# mgr.net
KiCad netlist of a schematic drawn in EAGLE
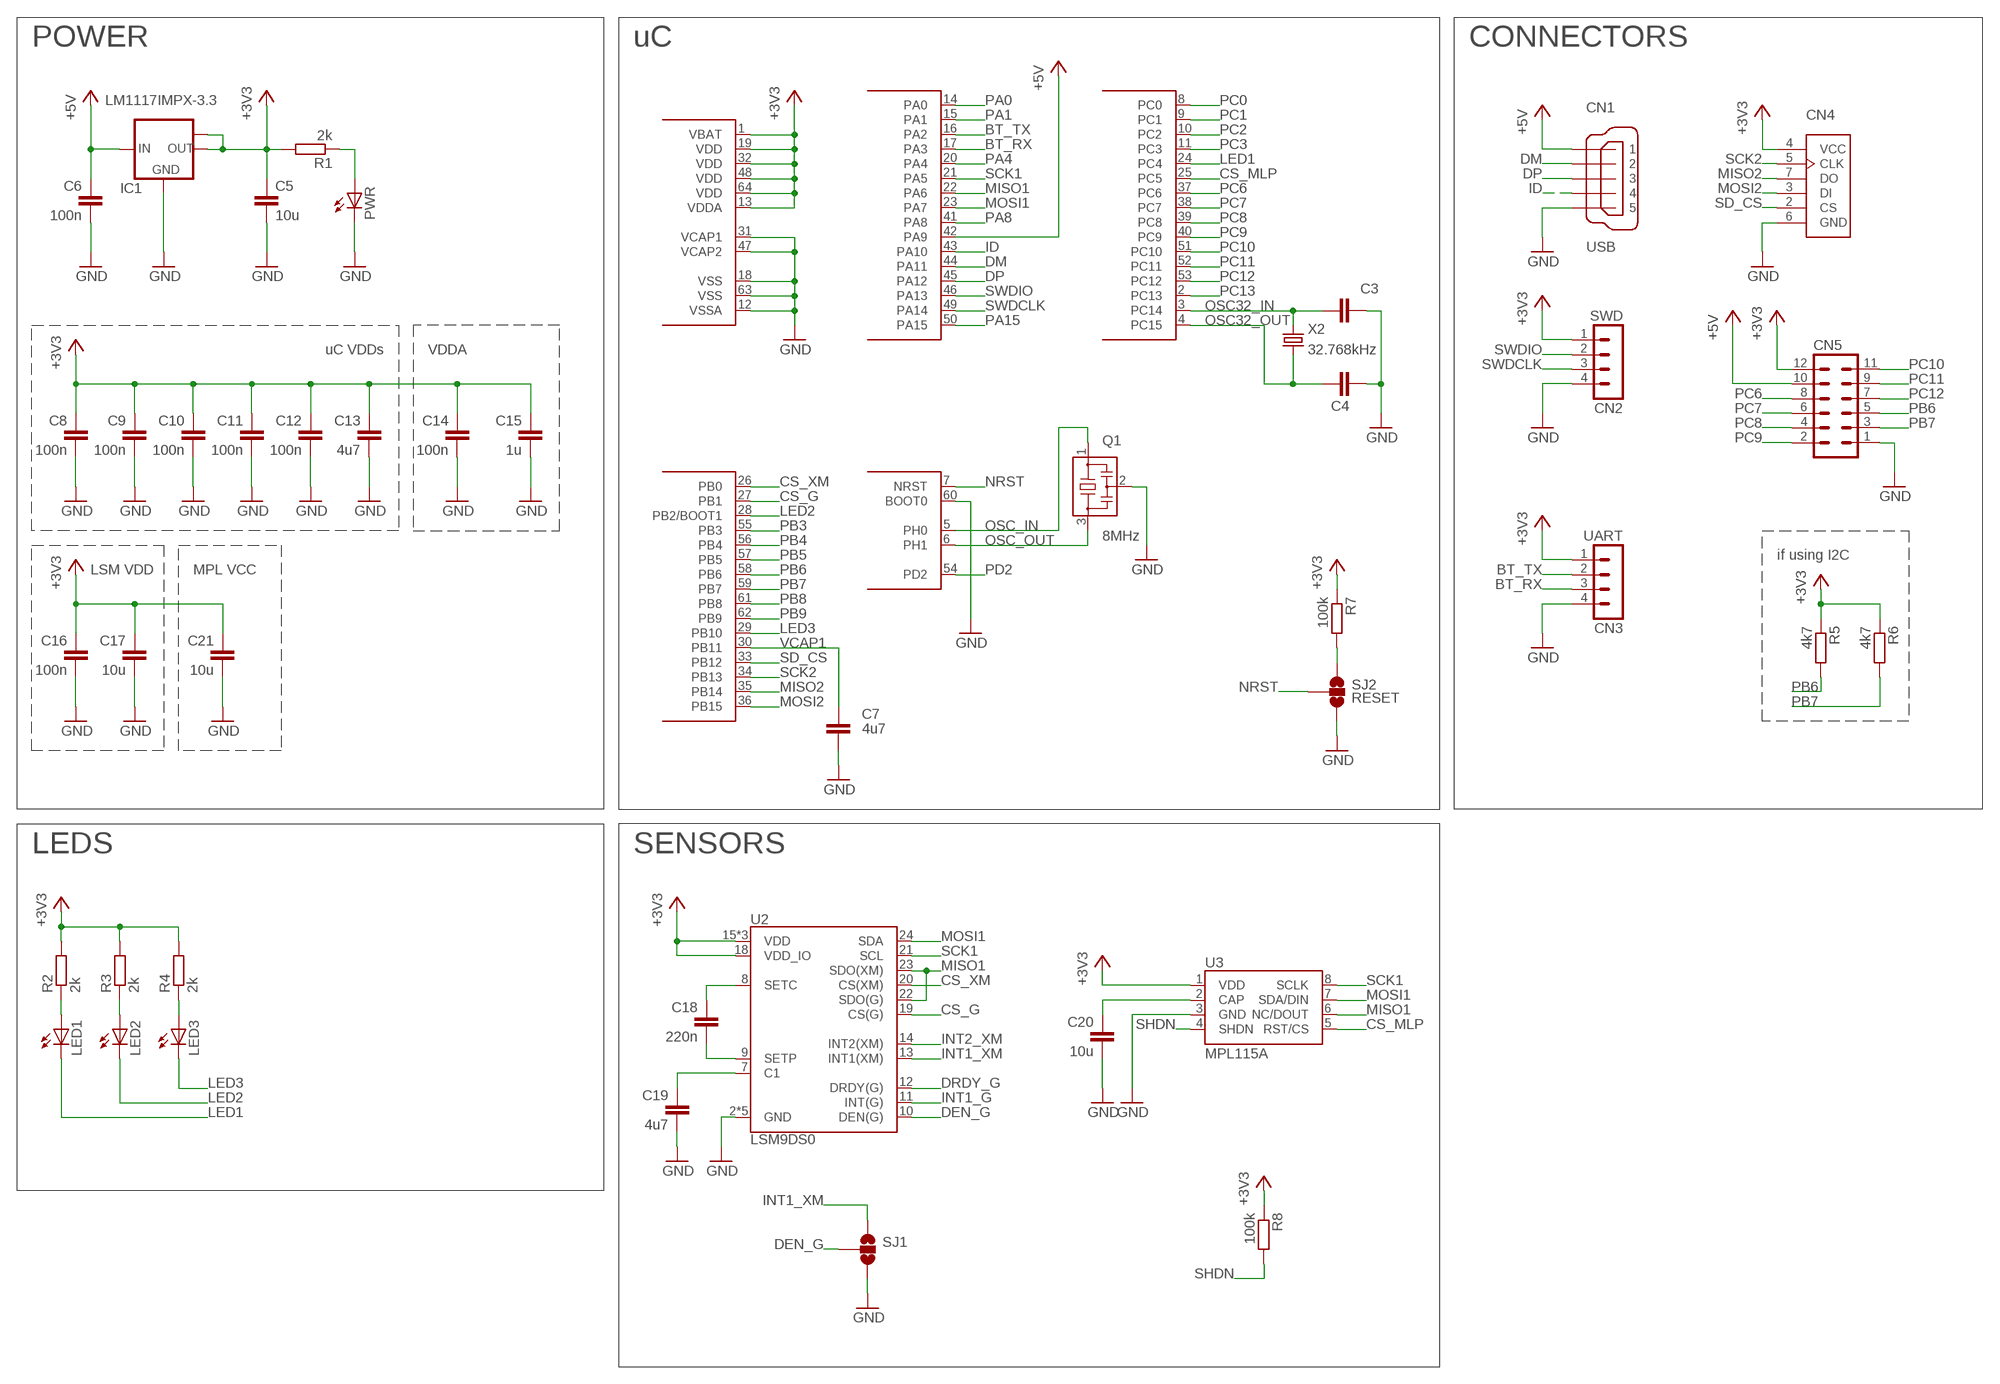
[diagram p0: schematic, sheet 1]

(export (version "E")
  (design (tool "Eeschema 10.0.6"))
  (components
    (comp (ref "C3")
      (value "C-EUC0603K")
      (footprint "eagle-import:C0603K")
      (libsource (lib "eagle-import") (part "C-EUC0603K"))
    )
    (comp (ref "C4")
      (value "C-EUC0603K")
      (footprint "eagle-import:C0603K")
      (libsource (lib "eagle-import") (part "C-EUC0603K"))
    )
    (comp (ref "C5")
      (value "10u")
      (footprint "eagle-import:C0603K")
      (libsource (lib "eagle-import") (part "C-EUC0603K"))
    )
    (comp (ref "C6")
      (value "100n")
      (footprint "eagle-import:C0603K")
      (libsource (lib "eagle-import") (part "C-EUC0603K"))
    )
    (comp (ref "C7")
      (value "4u7")
      (footprint "eagle-import:C0603K")
      (libsource (lib "eagle-import") (part "C-EUC0603K"))
    )
    (comp (ref "C8")
      (value "100n")
      (footprint "eagle-import:C0603K")
      (libsource (lib "eagle-import") (part "C-EUC0603K"))
    )
    (comp (ref "C9")
      (value "100n")
      (footprint "eagle-import:C0603K")
      (libsource (lib "eagle-import") (part "C-EUC0603K"))
    )
    (comp (ref "C10")
      (value "100n")
      (footprint "eagle-import:C0603K")
      (libsource (lib "eagle-import") (part "C-EUC0603K"))
    )
    (comp (ref "C11")
      (value "100n")
      (footprint "eagle-import:C0603K")
      (libsource (lib "eagle-import") (part "C-EUC0603K"))
    )
    (comp (ref "C12")
      (value "100n")
      (footprint "eagle-import:C0603K")
      (libsource (lib "eagle-import") (part "C-EUC0603K"))
    )
    (comp (ref "C13")
      (value "4u7")
      (footprint "eagle-import:C0603K")
      (libsource (lib "eagle-import") (part "C-EUC0603K"))
    )
    (comp (ref "C14")
      (value "100n")
      (footprint "eagle-import:C0603K")
      (libsource (lib "eagle-import") (part "C-EUC0603K"))
    )
    (comp (ref "C15")
      (value "1u")
      (footprint "eagle-import:C0603K")
      (libsource (lib "eagle-import") (part "C-EUC0603K"))
    )
    (comp (ref "C16")
      (value "100n")
      (footprint "eagle-import:C0603K")
      (libsource (lib "eagle-import") (part "C-EUC0603K"))
    )
    (comp (ref "C17")
      (value "10u")
      (footprint "eagle-import:C0603K")
      (libsource (lib "eagle-import") (part "C-EUC0603K"))
    )
    (comp (ref "C18")
      (value "220n")
      (footprint "eagle-import:C0603K")
      (libsource (lib "eagle-import") (part "C-EUC0603K"))
    )
    (comp (ref "C19")
      (value "4u7")
      (footprint "eagle-import:C0603K")
      (libsource (lib "eagle-import") (part "C-EUC0603K"))
    )
    (comp (ref "C20")
      (value "10u")
      (footprint "eagle-import:C0603K")
      (libsource (lib "eagle-import") (part "C-EUC0603K"))
    )
    (comp (ref "C21")
      (value "10u")
      (footprint "eagle-import:C0603K")
      (libsource (lib "eagle-import") (part "C-EUC0603K"))
    )
    (comp (ref "CN1")
      (value "USB")
      (footprint "eagle-import:UX60-MB-5ST")
      (libsource (lib "eagle-import") (part "MINI-USB-UX60-MB-5ST"))
    )
    (comp (ref "CN2")
      (value "SWD")
      (footprint "eagle-import:MA04-1")
      (libsource (lib "eagle-import") (part "MA04-1"))
    )
    (comp (ref "CN3")
      (value "UART")
      (footprint "eagle-import:MA04-1")
      (libsource (lib "eagle-import") (part "MA04-1"))
    )
    (comp (ref "CN4")
      (value "MICRO_SD_CONNECTOR")
      (footprint "eagle-import:MICROSD_CONNECTOR")
      (libsource (lib "eagle-import") (part "MICRO_SD_CONNECTOR"))
    )
    (comp (ref "CN5")
      (value "MA06-2")
      (footprint "eagle-import:MA06-2")
      (libsource (lib "eagle-import") (part "MA06-2"))
    )
    (comp (ref "IC1")
      (value "LM1117IMPX-3.3")
      (footprint "eagle-import:SOT223")
      (libsource (lib "eagle-import") (part "LM1117IMPX-3.3"))
    )
    (comp (ref "LED1")
      (value "LEDSML0603")
      (footprint "eagle-import:SML0603")
      (libsource (lib "eagle-import") (part "LEDSML0603"))
    )
    (comp (ref "LED2")
      (value "LEDSML0603")
      (footprint "eagle-import:SML0603")
      (libsource (lib "eagle-import") (part "LEDSML0603"))
    )
    (comp (ref "LED3")
      (value "LEDSML0603")
      (footprint "eagle-import:SML0603")
      (libsource (lib "eagle-import") (part "LEDSML0603"))
    )
    (comp (ref "PWR")
      (value "LEDSML0603")
      (footprint "eagle-import:SML0603")
      (libsource (lib "eagle-import") (part "LEDSML0603"))
    )
    (comp (ref "Q1")
      (value "8MHz")
      (footprint "eagle-import:CSTCR6M")
      (fields (field (name "MPN") "CSTCR6M00G53-R0"))
      (libsource (lib "eagle-import") (part "CSTCR6M00G53Z"))
    )
    (comp (ref "R1")
      (value "2k")
      (footprint "eagle-import:R0603")
      (libsource (lib "eagle-import") (part "R-EU_R0603"))
    )
    (comp (ref "R2")
      (value "2k")
      (footprint "eagle-import:R0603")
      (libsource (lib "eagle-import") (part "R-EU_R0603"))
    )
    (comp (ref "R3")
      (value "2k")
      (footprint "eagle-import:R0603")
      (libsource (lib "eagle-import") (part "R-EU_R0603"))
    )
    (comp (ref "R4")
      (value "2k")
      (footprint "eagle-import:R0603")
      (libsource (lib "eagle-import") (part "R-EU_R0603"))
    )
    (comp (ref "R5")
      (value "4k7")
      (footprint "eagle-import:R0603")
      (libsource (lib "eagle-import") (part "R-EU_R0603"))
    )
    (comp (ref "R6")
      (value "4k7")
      (footprint "eagle-import:R0603")
      (libsource (lib "eagle-import") (part "R-EU_R0603"))
    )
    (comp (ref "R7")
      (value "100k")
      (footprint "eagle-import:R0603")
      (libsource (lib "eagle-import") (part "R-EU_R0603"))
    )
    (comp (ref "R8")
      (value "100k")
      (footprint "eagle-import:R0603")
      (libsource (lib "eagle-import") (part "R-EU_R0603"))
    )
    (comp (ref "SJ1")
      (value "JUMPER-PAD-3-NOYES_SILK")
      (footprint "eagle-import:PAD-JUMPER-3-NO_YES_SILK")
      (libsource (lib "eagle-import") (part "JUMPER-PAD-3-NOYES_SILK"))
    )
    (comp (ref "SJ2")
      (value "RESET")
      (footprint "eagle-import:PAD-JUMPER-3-NO_YES_SILK")
      (libsource (lib "eagle-import") (part "JUMPER-PAD-3-NOYES_SILK"))
    )
    (comp (ref "U1")
      (value "STM32F4-64")
      (footprint "eagle-import:SQFP-S-10X10-64")
      (libsource (lib "eagle-import") (part "STM32F4-64"))
    )
    (comp (ref "U2")
      (value "LSM9DS0")
      (footprint "eagle-import:LGA-24")
      (libsource (lib "eagle-import") (part "LSM9DS0"))
    )
    (comp (ref "U3")
      (value "MPL115A")
      (footprint "eagle-import:LGA8")
      (libsource (lib "eagle-import") (part "MPL115A"))
    )
    (comp (ref "X2")
      (value "32.768kHz")
      (footprint "eagle-import:3.2X1.5-2-PAD")
      (libsource (lib "eagle-import") (part "CRYSTALS-NOGND-CFPX-217"))
    )
  )
  (nets
    (net (code "1") (name "+3V3") (class "Default")
      (node (ref "C10") (pin "2") (pinfunction "2_2") (pintype "passive"))
      (node (ref "C11") (pin "2") (pinfunction "2_2") (pintype "passive"))
      (node (ref "C12") (pin "2") (pinfunction "2_2") (pintype "passive"))
      (node (ref "C13") (pin "2") (pinfunction "2_2") (pintype "passive"))
      (node (ref "C14") (pin "2") (pinfunction "2_2") (pintype "passive"))
      (node (ref "C15") (pin "2") (pinfunction "2_2") (pintype "passive"))
      (node (ref "C16") (pin "2") (pinfunction "2_2") (pintype "passive"))
      (node (ref "C17") (pin "2") (pinfunction "2_2") (pintype "passive"))
      (node (ref "C21") (pin "2") (pinfunction "2_2") (pintype "passive"))
      (node (ref "C5") (pin "2") (pinfunction "2_2") (pintype "passive"))
      (node (ref "C8") (pin "2") (pinfunction "2_2") (pintype "passive"))
      (node (ref "C9") (pin "2") (pinfunction "2_2") (pintype "passive"))
      (node (ref "CN2") (pin "1") (pinfunction "1_1") (pintype "passive"))
      (node (ref "CN3") (pin "1") (pinfunction "1_1") (pintype "passive"))
      (node (ref "CN4") (pin "4") (pinfunction "VCC_4") (pintype "power_in"))
      (node (ref "CN5") (pin "12") (pinfunction "12_12") (pintype "passive"))
      (node (ref "IC1") (pin "2") (pinfunction "OUT_2") (pintype "passive"))
      (node (ref "IC1") (pin "TAB") (pinfunction "OUT1_TAB") (pintype "passive"))
      (node (ref "R1") (pin "2") (pinfunction "2_2") (pintype "passive"))
      (node (ref "R2") (pin "2") (pinfunction "2_2") (pintype "passive"))
      (node (ref "R3") (pin "2") (pinfunction "2_2") (pintype "passive"))
      (node (ref "R4") (pin "2") (pinfunction "2_2") (pintype "passive"))
      (node (ref "R5") (pin "1") (pinfunction "1_1") (pintype "passive"))
      (node (ref "R6") (pin "1") (pinfunction "1_1") (pintype "passive"))
      (node (ref "R7") (pin "1") (pinfunction "1_1") (pintype "passive"))
      (node (ref "R8") (pin "1") (pinfunction "1_1") (pintype "passive"))
      (node (ref "U1") (pin "1") (pinfunction "VBAT_1") (pintype "power_in"))
      (node (ref "U1") (pin "13") (pinfunction "VDDA_13") (pintype "power_in"))
      (node (ref "U1") (pin "19") (pinfunction "VDD_19") (pintype "power_in"))
      (node (ref "U1") (pin "32") (pinfunction "VDD_32") (pintype "power_in"))
      (node (ref "U1") (pin "48") (pinfunction "VDD_48") (pintype "power_in"))
      (node (ref "U1") (pin "64") (pinfunction "VDD_64") (pintype "power_in"))
      (node (ref "U2") (pin "15") (pinfunction "VDD_15") (pintype "bidirectional"))
      (node (ref "U2") (pin "16") (pinfunction "VDD_16") (pintype "bidirectional"))
      (node (ref "U2") (pin "17") (pinfunction "VDD_17") (pintype "bidirectional"))
      (node (ref "U2") (pin "18") (pinfunction "VDD_IO_18") (pintype "bidirectional"))
      (node (ref "U3") (pin "1") (pinfunction "VDD_1") (pintype "bidirectional"))
    )
    (net (code "2") (name "+5V") (class "Default")
      (node (ref "C6") (pin "2") (pinfunction "2_2") (pintype "passive"))
      (node (ref "CN1") (pin "1") (pinfunction "1_1") (pintype "input"))
      (node (ref "CN5") (pin "10") (pinfunction "10_10") (pintype "passive"))
      (node (ref "IC1") (pin "3") (pinfunction "IN_3") (pintype "input"))
      (node (ref "U1") (pin "42") (pinfunction "PA9_42") (pintype "bidirectional"))
    )
    (net (code "3") (name "/BT_RX") (class "Default")
      (node (ref "CN3") (pin "3") (pinfunction "3_3") (pintype "passive"))
      (node (ref "U1") (pin "17") (pinfunction "PA3_17") (pintype "bidirectional"))
    )
    (net (code "4") (name "/BT_TX") (class "Default")
      (node (ref "CN3") (pin "2") (pinfunction "2_2") (pintype "passive"))
      (node (ref "U1") (pin "16") (pinfunction "PA2_16") (pintype "bidirectional"))
    )
    (net (code "5") (name "/CS_G") (class "Default")
      (node (ref "U1") (pin "27") (pinfunction "PB1_27") (pintype "bidirectional"))
      (node (ref "U2") (pin "19") (pinfunction "CS(G)_19") (pintype "bidirectional"))
    )
    (net (code "6") (name "/CS_MLP") (class "Default")
      (node (ref "U1") (pin "25") (pinfunction "PC5_25") (pintype "bidirectional"))
      (node (ref "U3") (pin "5") (pinfunction "RST/CS_5") (pintype "bidirectional"))
    )
    (net (code "7") (name "/CS_XM") (class "Default")
      (node (ref "U1") (pin "26") (pinfunction "PB0_26") (pintype "bidirectional"))
      (node (ref "U2") (pin "20") (pinfunction "CS(XM)_20") (pintype "bidirectional"))
    )
    (net (code "8") (name "/DEN_G") (class "Default")
      (node (ref "SJ1") (pin "2") (pinfunction "2_2") (pintype "passive"))
      (node (ref "U2") (pin "10") (pinfunction "DEN(G)_10") (pintype "bidirectional"))
    )
    (net (code "9") (name "/DM") (class "Default")
      (node (ref "CN1") (pin "2") (pinfunction "2_2") (pintype "input"))
      (node (ref "U1") (pin "44") (pinfunction "PA11_44") (pintype "bidirectional"))
    )
    (net (code "10") (name "/DP") (class "Default")
      (node (ref "CN1") (pin "3") (pinfunction "3_3") (pintype "input"))
      (node (ref "U1") (pin "45") (pinfunction "PA12_45") (pintype "bidirectional"))
    )
    (net (code "11") (name "/DRDY_G") (class "Default")
      (node (ref "U2") (pin "12") (pinfunction "DRDY(G)_12") (pintype "bidirectional"))
    )
    (net (code "12") (name "/ID") (class "Default")
      (node (ref "CN1") (pin "4") (pinfunction "4_4") (pintype "input"))
      (node (ref "U1") (pin "43") (pinfunction "PA10_43") (pintype "bidirectional"))
    )
    (net (code "13") (name "/INT1_G") (class "Default")
      (node (ref "U2") (pin "11") (pinfunction "INT(G)_11") (pintype "bidirectional"))
    )
    (net (code "14") (name "/INT1_XM") (class "Default")
      (node (ref "SJ1") (pin "1") (pinfunction "1_1") (pintype "passive"))
      (node (ref "U2") (pin "13") (pinfunction "INT1(XM)_13") (pintype "bidirectional"))
    )
    (net (code "15") (name "/INT2_XM") (class "Default")
      (node (ref "U2") (pin "14") (pinfunction "INT2(XM)_14") (pintype "bidirectional"))
    )
    (net (code "16") (name "/LED1") (class "Default")
      (node (ref "LED1") (pin "C") (pinfunction "C_C") (pintype "passive"))
      (node (ref "U1") (pin "24") (pinfunction "PC4_24") (pintype "bidirectional"))
    )
    (net (code "17") (name "/LED2") (class "Default")
      (node (ref "LED2") (pin "C") (pinfunction "C_C") (pintype "passive"))
      (node (ref "U1") (pin "28") (pinfunction "PB2/BOOT1_28") (pintype "bidirectional"))
    )
    (net (code "18") (name "/LED3") (class "Default")
      (node (ref "LED3") (pin "C") (pinfunction "C_C") (pintype "passive"))
      (node (ref "U1") (pin "29") (pinfunction "PB10_29") (pintype "bidirectional"))
    )
    (net (code "19") (name "/MISO1") (class "Default")
      (node (ref "U1") (pin "22") (pinfunction "PA6_22") (pintype "bidirectional"))
      (node (ref "U2") (pin "22") (pinfunction "SDO(G)_22") (pintype "bidirectional"))
      (node (ref "U2") (pin "23") (pinfunction "SDO(XM)_23") (pintype "bidirectional"))
      (node (ref "U3") (pin "6") (pinfunction "NC/DOUT_6") (pintype "bidirectional"))
    )
    (net (code "20") (name "/MISO2") (class "Default")
      (node (ref "CN4") (pin "7") (pinfunction "DO_7") (pintype "output"))
      (node (ref "U1") (pin "35") (pinfunction "PB14_35") (pintype "bidirectional"))
    )
    (net (code "21") (name "/MOSI1") (class "Default")
      (node (ref "U1") (pin "23") (pinfunction "PA7_23") (pintype "bidirectional"))
      (node (ref "U2") (pin "24") (pinfunction "SDA_24") (pintype "bidirectional"))
      (node (ref "U3") (pin "7") (pinfunction "SDA/DIN_7") (pintype "bidirectional"))
    )
    (net (code "22") (name "/MOSI2") (class "Default")
      (node (ref "CN4") (pin "3") (pinfunction "DI_3") (pintype "input"))
      (node (ref "U1") (pin "36") (pinfunction "PB15_36") (pintype "bidirectional"))
    )
    (net (code "23") (name "/NRST") (class "Default")
      (node (ref "SJ2") (pin "2") (pinfunction "2_2") (pintype "passive"))
      (node (ref "U1") (pin "7") (pinfunction "NRST_7") (pintype "bidirectional"))
    )
    (net (code "24") (name "/OSC32_IN") (class "Default")
      (node (ref "C3") (pin "1") (pinfunction "1_1") (pintype "passive"))
      (node (ref "U1") (pin "3") (pinfunction "PC14_3") (pintype "bidirectional"))
      (node (ref "X2") (pin "1") (pinfunction "1_1") (pintype "passive"))
    )
    (net (code "25") (name "/OSC32_OUT") (class "Default")
      (node (ref "C4") (pin "1") (pinfunction "1_1") (pintype "passive"))
      (node (ref "U1") (pin "4") (pinfunction "PC15_4") (pintype "bidirectional"))
      (node (ref "X2") (pin "2") (pinfunction "2_2") (pintype "passive"))
    )
    (net (code "26") (name "/OSC_IN") (class "Default")
      (node (ref "Q1") (pin "1") (pinfunction "1_1") (pintype "passive"))
      (node (ref "U1") (pin "5") (pinfunction "PH0_5") (pintype "bidirectional"))
    )
    (net (code "27") (name "/OSC_OUT") (class "Default")
      (node (ref "Q1") (pin "3") (pinfunction "3_3") (pintype "passive"))
      (node (ref "U1") (pin "6") (pinfunction "PH1_6") (pintype "bidirectional"))
    )
    (net (code "28") (name "/PA0") (class "Default")
      (node (ref "U1") (pin "14") (pinfunction "PA0_14") (pintype "bidirectional"))
    )
    (net (code "29") (name "/PA1") (class "Default")
      (node (ref "U1") (pin "15") (pinfunction "PA1_15") (pintype "bidirectional"))
    )
    (net (code "30") (name "/PA4") (class "Default")
      (node (ref "U1") (pin "20") (pinfunction "PA4_20") (pintype "bidirectional"))
    )
    (net (code "31") (name "/PA8") (class "Default")
      (node (ref "U1") (pin "41") (pinfunction "PA8_41") (pintype "bidirectional"))
    )
    (net (code "32") (name "/PA15") (class "Default")
      (node (ref "U1") (pin "50") (pinfunction "PA15_50") (pintype "bidirectional"))
    )
    (net (code "33") (name "/PB3") (class "Default")
      (node (ref "U1") (pin "55") (pinfunction "PB3_55") (pintype "bidirectional"))
    )
    (net (code "34") (name "/PB4") (class "Default")
      (node (ref "U1") (pin "56") (pinfunction "PB4_56") (pintype "bidirectional"))
    )
    (net (code "35") (name "/PB5") (class "Default")
      (node (ref "U1") (pin "57") (pinfunction "PB5_57") (pintype "bidirectional"))
    )
    (net (code "36") (name "/PB6") (class "Default")
      (node (ref "CN5") (pin "5") (pinfunction "5_5") (pintype "passive"))
      (node (ref "R5") (pin "2") (pinfunction "2_2") (pintype "passive"))
      (node (ref "U1") (pin "58") (pinfunction "PB6_58") (pintype "bidirectional"))
    )
    (net (code "37") (name "/PB7") (class "Default")
      (node (ref "CN5") (pin "3") (pinfunction "3_3") (pintype "passive"))
      (node (ref "R6") (pin "2") (pinfunction "2_2") (pintype "passive"))
      (node (ref "U1") (pin "59") (pinfunction "PB7_59") (pintype "bidirectional"))
    )
    (net (code "38") (name "/PB8") (class "Default")
      (node (ref "U1") (pin "61") (pinfunction "PB8_61") (pintype "bidirectional"))
    )
    (net (code "39") (name "/PB9") (class "Default")
      (node (ref "U1") (pin "62") (pinfunction "PB9_62") (pintype "bidirectional"))
    )
    (net (code "40") (name "/PC0") (class "Default")
      (node (ref "U1") (pin "8") (pinfunction "PC0_8") (pintype "bidirectional"))
    )
    (net (code "41") (name "/PC1") (class "Default")
      (node (ref "U1") (pin "9") (pinfunction "PC1_9") (pintype "bidirectional"))
    )
    (net (code "42") (name "/PC2") (class "Default")
      (node (ref "U1") (pin "10") (pinfunction "PC2_10") (pintype "bidirectional"))
    )
    (net (code "43") (name "/PC3") (class "Default")
      (node (ref "U1") (pin "11") (pinfunction "PC3_11") (pintype "bidirectional"))
    )
    (net (code "44") (name "/PC6") (class "Default")
      (node (ref "CN5") (pin "8") (pinfunction "8_8") (pintype "passive"))
      (node (ref "U1") (pin "37") (pinfunction "PC6_37") (pintype "bidirectional"))
    )
    (net (code "45") (name "/PC7") (class "Default")
      (node (ref "CN5") (pin "6") (pinfunction "6_6") (pintype "passive"))
      (node (ref "U1") (pin "38") (pinfunction "PC7_38") (pintype "bidirectional"))
    )
    (net (code "46") (name "/PC8") (class "Default")
      (node (ref "CN5") (pin "4") (pinfunction "4_4") (pintype "passive"))
      (node (ref "U1") (pin "39") (pinfunction "PC8_39") (pintype "bidirectional"))
    )
    (net (code "47") (name "/PC9") (class "Default")
      (node (ref "CN5") (pin "2") (pinfunction "2_2") (pintype "passive"))
      (node (ref "U1") (pin "40") (pinfunction "PC9_40") (pintype "bidirectional"))
    )
    (net (code "48") (name "/PC10") (class "Default")
      (node (ref "CN5") (pin "11") (pinfunction "11_11") (pintype "passive"))
      (node (ref "U1") (pin "51") (pinfunction "PC10_51") (pintype "bidirectional"))
    )
    (net (code "49") (name "/PC11") (class "Default")
      (node (ref "CN5") (pin "9") (pinfunction "9_9") (pintype "passive"))
      (node (ref "U1") (pin "52") (pinfunction "PC11_52") (pintype "bidirectional"))
    )
    (net (code "50") (name "/PC12") (class "Default")
      (node (ref "CN5") (pin "7") (pinfunction "7_7") (pintype "passive"))
      (node (ref "U1") (pin "53") (pinfunction "PC12_53") (pintype "bidirectional"))
    )
    (net (code "51") (name "/PC13") (class "Default")
      (node (ref "U1") (pin "2") (pinfunction "PC13_2") (pintype "bidirectional"))
    )
    (net (code "52") (name "/PD2") (class "Default")
      (node (ref "U1") (pin "54") (pinfunction "PD2_54") (pintype "bidirectional"))
    )
    (net (code "53") (name "/SCK1") (class "Default")
      (node (ref "U1") (pin "21") (pinfunction "PA5_21") (pintype "bidirectional"))
      (node (ref "U2") (pin "21") (pinfunction "SCL_21") (pintype "bidirectional"))
      (node (ref "U3") (pin "8") (pinfunction "SCLK_8") (pintype "bidirectional"))
    )
    (net (code "54") (name "/SCK2") (class "Default")
      (node (ref "CN4") (pin "5") (pinfunction "CLK_5") (pintype "input"))
      (node (ref "U1") (pin "34") (pinfunction "PB13_34") (pintype "bidirectional"))
    )
    (net (code "55") (name "/SD_CS") (class "Default")
      (node (ref "CN4") (pin "2") (pinfunction "CS_2") (pintype "input"))
      (node (ref "U1") (pin "33") (pinfunction "PB12_33") (pintype "bidirectional"))
    )
    (net (code "56") (name "/SHDN") (class "Default")
      (node (ref "R8") (pin "2") (pinfunction "2_2") (pintype "passive"))
      (node (ref "U3") (pin "4") (pinfunction "SHDN_4") (pintype "bidirectional"))
    )
    (net (code "57") (name "/SWDCLK") (class "Default")
      (node (ref "CN2") (pin "3") (pinfunction "3_3") (pintype "passive"))
      (node (ref "U1") (pin "49") (pinfunction "PA14_49") (pintype "bidirectional"))
    )
    (net (code "58") (name "/SWDIO") (class "Default")
      (node (ref "CN2") (pin "2") (pinfunction "2_2") (pintype "passive"))
      (node (ref "U1") (pin "46") (pinfunction "PA13_46") (pintype "bidirectional"))
    )
    (net (code "59") (name "/VCAP1") (class "Default")
      (node (ref "C7") (pin "1") (pinfunction "1_1") (pintype "passive"))
      (node (ref "U1") (pin "30") (pinfunction "PB11_30") (pintype "bidirectional"))
    )
    (net (code "60") (name "GND") (class "Default")
      (node (ref "C10") (pin "1") (pinfunction "1_1") (pintype "passive"))
      (node (ref "C11") (pin "1") (pinfunction "1_1") (pintype "passive"))
      (node (ref "C12") (pin "1") (pinfunction "1_1") (pintype "passive"))
      (node (ref "C13") (pin "1") (pinfunction "1_1") (pintype "passive"))
      (node (ref "C14") (pin "1") (pinfunction "1_1") (pintype "passive"))
      (node (ref "C15") (pin "1") (pinfunction "1_1") (pintype "passive"))
      (node (ref "C16") (pin "1") (pinfunction "1_1") (pintype "passive"))
      (node (ref "C17") (pin "1") (pinfunction "1_1") (pintype "passive"))
      (node (ref "C19") (pin "1") (pinfunction "1_1") (pintype "passive"))
      (node (ref "C20") (pin "1") (pinfunction "1_1") (pintype "passive"))
      (node (ref "C21") (pin "1") (pinfunction "1_1") (pintype "passive"))
      (node (ref "C3") (pin "2") (pinfunction "2_2") (pintype "passive"))
      (node (ref "C4") (pin "2") (pinfunction "2_2") (pintype "passive"))
      (node (ref "C5") (pin "1") (pinfunction "1_1") (pintype "passive"))
      (node (ref "C6") (pin "1") (pinfunction "1_1") (pintype "passive"))
      (node (ref "C7") (pin "2") (pinfunction "2_2") (pintype "passive"))
      (node (ref "C8") (pin "1") (pinfunction "1_1") (pintype "passive"))
      (node (ref "C9") (pin "1") (pinfunction "1_1") (pintype "passive"))
      (node (ref "CN1") (pin "5") (pinfunction "5_5") (pintype "input"))
      (node (ref "CN2") (pin "4") (pinfunction "4_4") (pintype "passive"))
      (node (ref "CN3") (pin "4") (pinfunction "4_4") (pintype "passive"))
      (node (ref "CN4") (pin "6") (pinfunction "GND_6") (pintype "bidirectional"))
      (node (ref "CN5") (pin "1") (pinfunction "1_1") (pintype "passive"))
      (node (ref "IC1") (pin "1") (pinfunction "GND_1") (pintype "input"))
      (node (ref "PWR") (pin "C") (pinfunction "C_C") (pintype "passive"))
      (node (ref "Q1") (pin "2") (pinfunction "2_2") (pintype "passive"))
      (node (ref "SJ1") (pin "3") (pinfunction "3_3") (pintype "passive"))
      (node (ref "SJ2") (pin "3") (pinfunction "3_3") (pintype "passive"))
      (node (ref "U1") (pin "12") (pinfunction "VSSA_12") (pintype "power_in"))
      (node (ref "U1") (pin "18") (pinfunction "VSS_18") (pintype "power_in"))
      (node (ref "U1") (pin "31") (pinfunction "VCAP1_31") (pintype "passive"))
      (node (ref "U1") (pin "47") (pinfunction "VCAP2_47") (pintype "passive"))
      (node (ref "U1") (pin "60") (pinfunction "BOOT0_60") (pintype "bidirectional"))
      (node (ref "U1") (pin "63") (pinfunction "VSS_63") (pintype "power_in"))
      (node (ref "U2") (pin "2") (pinfunction "GND_2") (pintype "bidirectional"))
      (node (ref "U2") (pin "3") (pinfunction "GND_3") (pintype "bidirectional"))
      (node (ref "U2") (pin "4") (pinfunction "GND_4") (pintype "bidirectional"))
      (node (ref "U2") (pin "5") (pinfunction "GND_5") (pintype "bidirectional"))
      (node (ref "U2") (pin "6") (pinfunction "GND_6") (pintype "bidirectional"))
      (node (ref "U3") (pin "3") (pinfunction "GND_3") (pintype "bidirectional"))
    )
    (net (code "61") (name "Net-(LED1-PadA)") (class "Default")
      (node (ref "LED1") (pin "A") (pinfunction "A_A") (pintype "passive"))
      (node (ref "R2") (pin "1") (pinfunction "1_1") (pintype "passive"))
    )
    (net (code "62") (name "Net-(LED2-PadA)") (class "Default")
      (node (ref "LED2") (pin "A") (pinfunction "A_A") (pintype "passive"))
      (node (ref "R3") (pin "1") (pinfunction "1_1") (pintype "passive"))
    )
    (net (code "63") (name "Net-(LED3-PadA)") (class "Default")
      (node (ref "LED3") (pin "A") (pinfunction "A_A") (pintype "passive"))
      (node (ref "R4") (pin "1") (pinfunction "1_1") (pintype "passive"))
    )
    (net (code "64") (name "Net-(PWR-PadA)") (class "Default")
      (node (ref "PWR") (pin "A") (pinfunction "A_A") (pintype "passive"))
      (node (ref "R1") (pin "1") (pinfunction "1_1") (pintype "passive"))
    )
    (net (code "65") (name "Net-(R7-Pad2)") (class "Default")
      (node (ref "R7") (pin "2") (pinfunction "2_2") (pintype "passive"))
      (node (ref "SJ2") (pin "1") (pinfunction "1_1") (pintype "passive"))
    )
    (net (code "66") (name "Net-(U2-C1)") (class "Default")
      (node (ref "C19") (pin "2") (pinfunction "2_2") (pintype "passive"))
      (node (ref "U2") (pin "7") (pinfunction "C1_7") (pintype "bidirectional"))
    )
    (net (code "67") (name "Net-(U2-SETC)") (class "Default")
      (node (ref "C18") (pin "2") (pinfunction "2_2") (pintype "passive"))
      (node (ref "U2") (pin "8") (pinfunction "SETC_8") (pintype "bidirectional"))
    )
    (net (code "68") (name "Net-(U2-SETP)") (class "Default")
      (node (ref "C18") (pin "1") (pinfunction "1_1") (pintype "passive"))
      (node (ref "U2") (pin "9") (pinfunction "SETP_9") (pintype "bidirectional"))
    )
    (net (code "69") (name "Net-(U3-CAP)") (class "Default")
      (node (ref "C20") (pin "2") (pinfunction "2_2") (pintype "passive"))
      (node (ref "U3") (pin "2") (pinfunction "CAP_2") (pintype "bidirectional"))
    )
  )
)
